# Connectors.net
KiCad netlist of a schematic drawn in Altium Designer
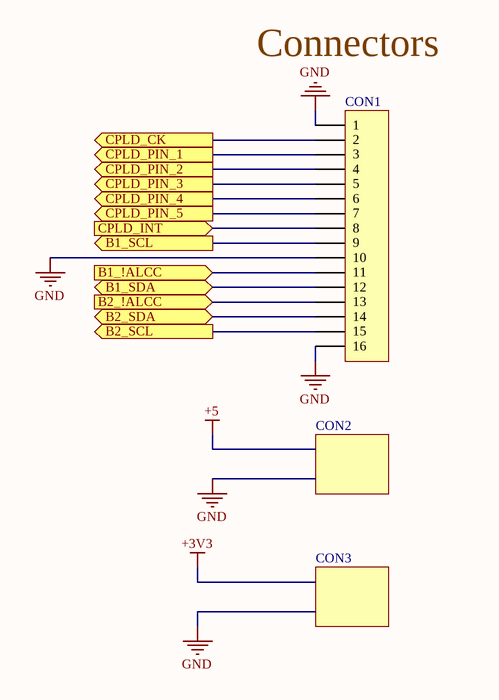
[diagram p0: Connectors.SchDoc]

(export (version "E")
  (design (tool "Eeschema 10.0.6"))
  (components
    (comp (ref "CON1")
      (value "Header 16")
      (footprint "HDR1X16")
      (description "Header, 16-Pin")
      (fields (field (name "PUBLISHER") "Altium Limited"))
      (libsource (lib "BMS_Schematic") (part "Header 16"))
    )
    (comp (ref "CON2")
      (value "Bornier_1")
      (footprint "Block_2Position")
      (description "Bornier à vis")
      (libsource (lib "BMS_Schematic") (part "Bornier_1"))
    )
    (comp (ref "CON3")
      (value "Bornier_1")
      (footprint "Block_2Position")
      (description "Bornier à vis")
      (libsource (lib "BMS_Schematic") (part "Bornier_1"))
    )
  )
  (nets
    (net (code "1") (name "+3V3") (class "Default")
      (node (ref "CON3") (pin "1") (pinfunction "1_1") (pintype "passive"))
    )
    (net (code "2") (name "+5") (class "Default")
      (node (ref "CON2") (pin "1") (pinfunction "1_1") (pintype "passive"))
    )
    (net (code "3") (name "/B1_!ALCC") (class "Default")
      (node (ref "CON1") (pin "11") (pinfunction "11_11") (pintype "passive"))
    )
    (net (code "4") (name "/B1_SCL") (class "Default")
      (node (ref "CON1") (pin "9") (pinfunction "9_9") (pintype "passive"))
    )
    (net (code "5") (name "/B1_SDA") (class "Default")
      (node (ref "CON1") (pin "12") (pinfunction "12_12") (pintype "passive"))
    )
    (net (code "6") (name "/B2_!ALCC") (class "Default")
      (node (ref "CON1") (pin "13") (pinfunction "13_13") (pintype "passive"))
    )
    (net (code "7") (name "/B2_SCL") (class "Default")
      (node (ref "CON1") (pin "15") (pinfunction "15_15") (pintype "passive"))
    )
    (net (code "8") (name "/B2_SDA") (class "Default")
      (node (ref "CON1") (pin "14") (pinfunction "14_14") (pintype "passive"))
    )
    (net (code "9") (name "/CPLD_CK") (class "Default")
      (node (ref "CON1") (pin "2") (pinfunction "2_2") (pintype "passive"))
    )
    (net (code "10") (name "/CPLD_INT") (class "Default")
      (node (ref "CON1") (pin "8") (pinfunction "8_8") (pintype "passive"))
    )
    (net (code "11") (name "/CPLD_PIN_1") (class "Default")
      (node (ref "CON1") (pin "3") (pinfunction "3_3") (pintype "passive"))
    )
    (net (code "12") (name "/CPLD_PIN_2") (class "Default")
      (node (ref "CON1") (pin "4") (pinfunction "4_4") (pintype "passive"))
    )
    (net (code "13") (name "/CPLD_PIN_3") (class "Default")
      (node (ref "CON1") (pin "5") (pinfunction "5_5") (pintype "passive"))
    )
    (net (code "14") (name "/CPLD_PIN_4") (class "Default")
      (node (ref "CON1") (pin "6") (pinfunction "6_6") (pintype "passive"))
    )
    (net (code "15") (name "/CPLD_PIN_5") (class "Default")
      (node (ref "CON1") (pin "7") (pinfunction "7_7") (pintype "passive"))
    )
    (net (code "16") (name "GND") (class "Default")
      (node (ref "CON1") (pin "1") (pinfunction "1_1") (pintype "passive"))
      (node (ref "CON1") (pin "10") (pinfunction "10_10") (pintype "passive"))
      (node (ref "CON1") (pin "16") (pinfunction "16_16") (pintype "passive"))
      (node (ref "CON2") (pin "2") (pinfunction "2_2") (pintype "passive"))
      (node (ref "CON3") (pin "2") (pinfunction "2_2") (pintype "passive"))
    )
  )
)
